# Sensors.net
KiCad netlist of a schematic drawn in Altium Designer
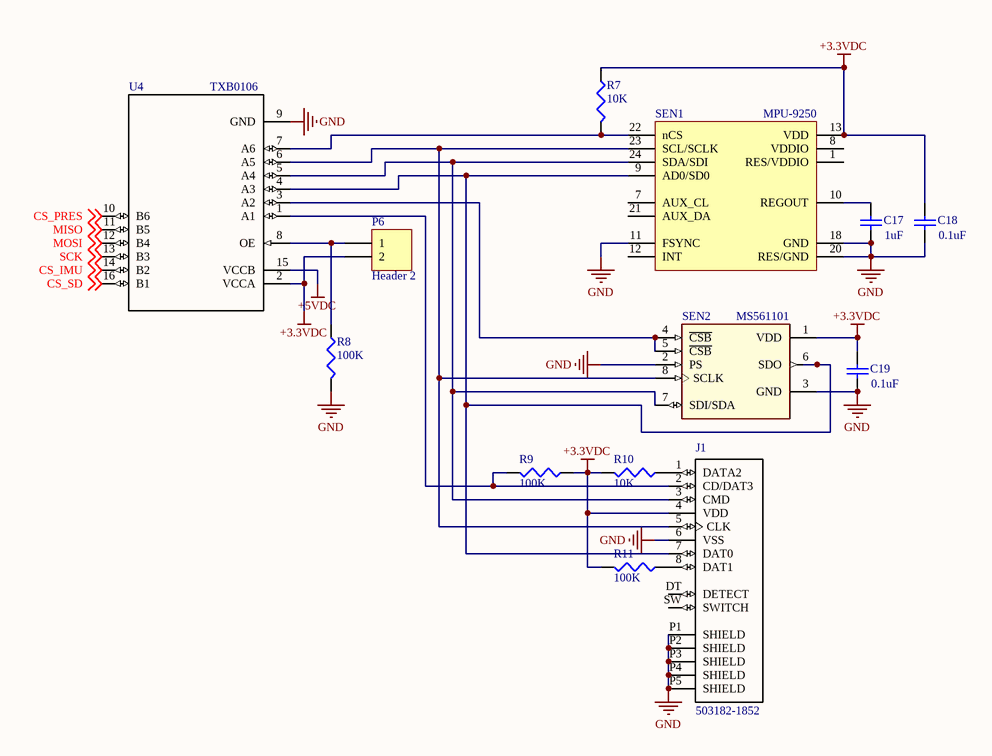
[diagram p0: Sensors.SchDoc]

(export (version "E")
  (design (tool "Eeschema 10.0.6"))
  (components
    (comp (ref "C17")
      (value "1uF")
      (footprint "1608[0603]")
      (description "Capacitor (Semiconductor SIM Model)")
      (fields (field (name "Comment") "Cap Semi") (field (name "PUBLISHER") "Altium Limited"))
      (libsource (lib "Miscellaneous Devices") (part "Cap Semi"))
    )
    (comp (ref "C18")
      (value "0.1uF")
      (footprint "1608[0603]")
      (description "Capacitor (Semiconductor SIM Model)")
      (fields (field (name "Comment") "Cap Semi") (field (name "PUBLISHER") "Altium Limited"))
      (libsource (lib "Miscellaneous Devices") (part "Cap Semi"))
    )
    (comp (ref "C19")
      (value "0.1uF")
      (footprint "1608[0603]")
      (description "Capacitor (Semiconductor SIM Model)")
      (fields (field (name "Comment") "Cap Semi") (field (name "PUBLISHER") "Altium Limited"))
      (libsource (lib "Miscellaneous Devices") (part "Cap Semi"))
    )
    (comp (ref "J1")
      (value "503182-1852")
      (footprint "MOLEX_503182-1852_503182-1852(Primary)")
      (description "Conn Micro SD Card M 8 POS 1.09mm Solder RA SMD Embossed T/R 0.5A/Contact")
      (fields (field (name "MF") "Molex"))
      (libsource (lib "503182-1852") (part "microSD Slot"))
    )
    (comp (ref "P6")
      (value "Header 2")
      (footprint "HDR1X2")
      (description "Header, 2-Pin")
      (fields (field (name "PUBLISHER") "Altium Limited"))
      (libsource (lib "Miscellaneous Connectors") (part "Header 2"))
    )
    (comp (ref "R7")
      (value "10K")
      (footprint "J1-0603")
      (description "Resistor")
      (fields (field (name "Comment") "Res3") (field (name "PUBLISHER") "Altium Limited"))
      (libsource (lib "Miscellaneous Devices") (part "Res3"))
    )
    (comp (ref "R8")
      (value "100K")
      (footprint "J1-0603")
      (description "Resistor")
      (fields (field (name "Comment") "Res3") (field (name "PUBLISHER") "Altium Limited"))
      (libsource (lib "Miscellaneous Devices") (part "Res3"))
    )
    (comp (ref "R9")
      (value "100K")
      (footprint "J1-0603")
      (description "Resistor")
      (fields (field (name "Comment") "Res3") (field (name "PUBLISHER") "Altium Limited"))
      (libsource (lib "Miscellaneous Devices") (part "Res3"))
    )
    (comp (ref "R10")
      (value "10K")
      (footprint "J1-0603")
      (description "Resistor")
      (fields (field (name "Comment") "Res3") (field (name "PUBLISHER") "Altium Limited"))
      (libsource (lib "Miscellaneous Devices") (part "Res3"))
    )
    (comp (ref "R11")
      (value "100K")
      (footprint "J1-0603")
      (description "Resistor")
      (fields (field (name "Comment") "Res3") (field (name "PUBLISHER") "Altium Limited"))
      (libsource (lib "Miscellaneous Devices") (part "Res3"))
    )
    (comp (ref "SEN1")
      (value "MPU-9250")
      (footprint "QFN40P300X300X105_HS-25L")
      (libsource (lib "CustomCompLib") (part "MPU-9250"))
    )
    (comp (ref "SEN2")
      (value "MS561101")
      (footprint "SON125P500X300X100-8N")
      (description "Pressure Sensor 1.44V to 3.6V 0.01bar to 1.2bar Absolute 8-Pin QFN T/R")
      (fields (field (name "MF") "TE Connectivity") (field (name "MP") "MS561101BA03-50"))
      (libsource (lib "MS561101BA03-50") (part "MS561101BA03-50"))
    )
    (comp (ref "U4")
      (value "TXB0106")
      (footprint "SOP65P640X120-16N")
      (fields (field (name "MP") "TXB0106PWR") (field (name "MF") "Texas Instruments"))
      (libsource (lib "TXB0106PWR") (part "TXB0106PWR"))
    )
  )
  (nets
    (net (code "1") (name "+3.3VDC") (class "Default")
      (node (ref "C18") (pin "2") (pinfunction "2_2") (pintype "passive"))
      (node (ref "C19") (pin "2") (pinfunction "2_2") (pintype "passive"))
      (node (ref "J1") (pin "4") (pinfunction "VDD_4") (pintype "power_in"))
      (node (ref "P6") (pin "2") (pinfunction "2_2") (pintype "passive"))
      (node (ref "R10") (pin "2") (pinfunction "2_2") (pintype "passive"))
      (node (ref "R11") (pin "2") (pinfunction "2_2") (pintype "passive"))
      (node (ref "R7") (pin "1") (pinfunction "1_1") (pintype "passive"))
      (node (ref "R9") (pin "1") (pinfunction "1_1") (pintype "passive"))
      (node (ref "SEN1") (pin "13") (pinfunction "VDD_13") (pintype "passive"))
      (node (ref "SEN2") (pin "1") (pinfunction "VDD_1") (pintype "power_in"))
      (node (ref "U4") (pin "2") (pinfunction "VCCA_2") (pintype "power_in"))
    )
    (net (code "2") (name "+5VDC") (class "Default")
      (node (ref "U4") (pin "15") (pinfunction "VCCB_15") (pintype "power_in"))
    )
    (net (code "3") (name "CS_IMU") (class "Default")
      (node (ref "U4") (pin "14") (pinfunction "B2_14") (pintype "bidirectional"))
    )
    (net (code "4") (name "CS_PRES") (class "Default")
      (node (ref "U4") (pin "10") (pinfunction "B6_10") (pintype "bidirectional"))
    )
    (net (code "5") (name "CS_SD") (class "Default")
      (node (ref "U4") (pin "16") (pinfunction "B1_16") (pintype "bidirectional"))
    )
    (net (code "6") (name "GND") (class "Default")
      (node (ref "C17") (pin "1") (pinfunction "1_1") (pintype "passive"))
      (node (ref "C18") (pin "1") (pinfunction "1_1") (pintype "passive"))
      (node (ref "C19") (pin "1") (pinfunction "1_1") (pintype "passive"))
      (node (ref "J1") (pin "6") (pinfunction "VSS_6") (pintype "power_in"))
      (node (ref "J1") (pin "P1") (pinfunction "SHIELD_P1") (pintype "passive"))
      (node (ref "J1") (pin "P2") (pinfunction "SHIELD_P2") (pintype "passive"))
      (node (ref "J1") (pin "P3") (pinfunction "SHIELD_P3") (pintype "passive"))
      (node (ref "J1") (pin "P4") (pinfunction "SHIELD_P4") (pintype "passive"))
      (node (ref "J1") (pin "P5") (pinfunction "SHIELD_P5") (pintype "passive"))
      (node (ref "R8") (pin "2") (pinfunction "2_2") (pintype "passive"))
      (node (ref "SEN1") (pin "11") (pinfunction "FSYNC_11") (pintype "passive"))
      (node (ref "SEN1") (pin "18") (pinfunction "GND_18") (pintype "passive"))
      (node (ref "SEN1") (pin "20") (pinfunction "RES/GND_20") (pintype "passive"))
      (node (ref "SEN2") (pin "2") (pinfunction "PS_2") (pintype "input"))
      (node (ref "SEN2") (pin "3") (pinfunction "GND_3") (pintype "power_in"))
      (node (ref "U4") (pin "9") (pinfunction "GND_9") (pintype "passive"))
    )
    (net (code "7") (name "MISO") (class "Default")
      (node (ref "U4") (pin "11") (pinfunction "B5_11") (pintype "bidirectional"))
    )
    (net (code "8") (name "MOSI") (class "Default")
      (node (ref "U4") (pin "12") (pinfunction "B4_12") (pintype "bidirectional"))
    )
    (net (code "9") (name "Net-(J1-CD{slash}DAT3)") (class "Default")
      (node (ref "J1") (pin "2") (pinfunction "CD/DAT3_2") (pintype "bidirectional"))
      (node (ref "R9") (pin "2") (pinfunction "2_2") (pintype "passive"))
      (node (ref "U4") (pin "1") (pinfunction "A1_1") (pintype "bidirectional"))
    )
    (net (code "10") (name "Net-(J1-CLK)") (class "Default")
      (node (ref "J1") (pin "5") (pinfunction "CLK_5") (pintype "bidirectional"))
      (node (ref "SEN1") (pin "23") (pinfunction "SCL/SCLK_23") (pintype "passive"))
      (node (ref "SEN2") (pin "8") (pinfunction "SCLK_8") (pintype "input"))
      (node (ref "U4") (pin "6") (pinfunction "A5_6") (pintype "bidirectional"))
    )
    (net (code "11") (name "Net-(J1-CMD)") (class "Default")
      (node (ref "J1") (pin "3") (pinfunction "CMD_3") (pintype "bidirectional"))
      (node (ref "SEN1") (pin "24") (pinfunction "SDA/SDI_24") (pintype "passive"))
      (node (ref "SEN2") (pin "7") (pinfunction "SDI/SDA_7") (pintype "bidirectional"))
      (node (ref "U4") (pin "5") (pinfunction "A4_5") (pintype "bidirectional"))
    )
    (net (code "12") (name "Net-(J1-DAT0)") (class "Default")
      (node (ref "J1") (pin "7") (pinfunction "DAT0_7") (pintype "bidirectional"))
      (node (ref "SEN1") (pin "9") (pinfunction "AD0/SD0_9") (pintype "passive"))
      (node (ref "SEN2") (pin "6") (pinfunction "SDO_6") (pintype "output"))
      (node (ref "U4") (pin "4") (pinfunction "A3_4") (pintype "bidirectional"))
    )
    (net (code "13") (name "Net-(J1-DAT1)") (class "Default")
      (node (ref "J1") (pin "8") (pinfunction "DAT1_8") (pintype "bidirectional"))
      (node (ref "R11") (pin "1") (pinfunction "1_1") (pintype "passive"))
    )
    (net (code "14") (name "Net-(J1-DATA2)") (class "Default")
      (node (ref "J1") (pin "1") (pinfunction "DATA2_1") (pintype "bidirectional"))
      (node (ref "R10") (pin "1") (pinfunction "1_1") (pintype "passive"))
    )
    (net (code "15") (name "Net-(SEN1-REGOUT)") (class "Default")
      (node (ref "C17") (pin "2") (pinfunction "2_2") (pintype "passive"))
      (node (ref "SEN1") (pin "10") (pinfunction "REGOUT_10") (pintype "passive"))
    )
    (net (code "16") (name "Net-(SEN1-nCS)") (class "Default")
      (node (ref "R7") (pin "2") (pinfunction "2_2") (pintype "passive"))
      (node (ref "SEN1") (pin "22") (pinfunction "nCS_22") (pintype "passive"))
      (node (ref "U4") (pin "7") (pinfunction "A6_7") (pintype "bidirectional"))
    )
    (net (code "17") (name "Net-(U4-A2)") (class "Default")
      (node (ref "SEN2") (pin "4") (pinfunction "~{CSB}_4") (pintype "input"))
      (node (ref "SEN2") (pin "5") (pinfunction "~{CSB}_5") (pintype "input"))
      (node (ref "U4") (pin "3") (pinfunction "A2_3") (pintype "bidirectional"))
    )
    (net (code "18") (name "Net-(U4-OE)") (class "Default")
      (node (ref "P6") (pin "1") (pinfunction "1_1") (pintype "passive"))
      (node (ref "R8") (pin "1") (pinfunction "1_1") (pintype "passive"))
      (node (ref "U4") (pin "8") (pinfunction "OE_8") (pintype "input"))
    )
    (net (code "19") (name "SCK") (class "Default")
      (node (ref "U4") (pin "13") (pinfunction "B3_13") (pintype "bidirectional"))
    )
    (net (code "20") (name "unconnected-(J1-DETECT-PadDT)") (class "Default")
      (node (ref "J1") (pin "DT") (pinfunction "DETECT_DT") (pintype "bidirectional"))
    )
    (net (code "21") (name "unconnected-(J1-SWITCH-PadSW)") (class "Default")
      (node (ref "J1") (pin "SW") (pinfunction "SWITCH_SW") (pintype "bidirectional"))
    )
    (net (code "22") (name "unconnected-(SEN1-AUX_CL-Pad7)") (class "Default")
      (node (ref "SEN1") (pin "7") (pinfunction "AUX_CL_7") (pintype "passive"))
    )
    (net (code "23") (name "unconnected-(SEN1-AUX_DA-Pad21)") (class "Default")
      (node (ref "SEN1") (pin "21") (pinfunction "AUX_DA_21") (pintype "passive"))
    )
    (net (code "24") (name "unconnected-(SEN1-INT-Pad12)") (class "Default")
      (node (ref "SEN1") (pin "12") (pinfunction "INT_12") (pintype "passive"))
    )
    (net (code "25") (name "unconnected-(SEN1-RES{slash}VDDIO-Pad1)") (class "Default")
      (node (ref "SEN1") (pin "1") (pinfunction "RES/VDDIO_1") (pintype "passive"))
    )
    (net (code "26") (name "unconnected-(SEN1-VDDIO-Pad8)") (class "Default")
      (node (ref "SEN1") (pin "8") (pinfunction "VDDIO_8") (pintype "passive"))
    )
  )
)
